# SCB_CLKs.net
KiCad netlist of a schematic drawn in Altium Designer
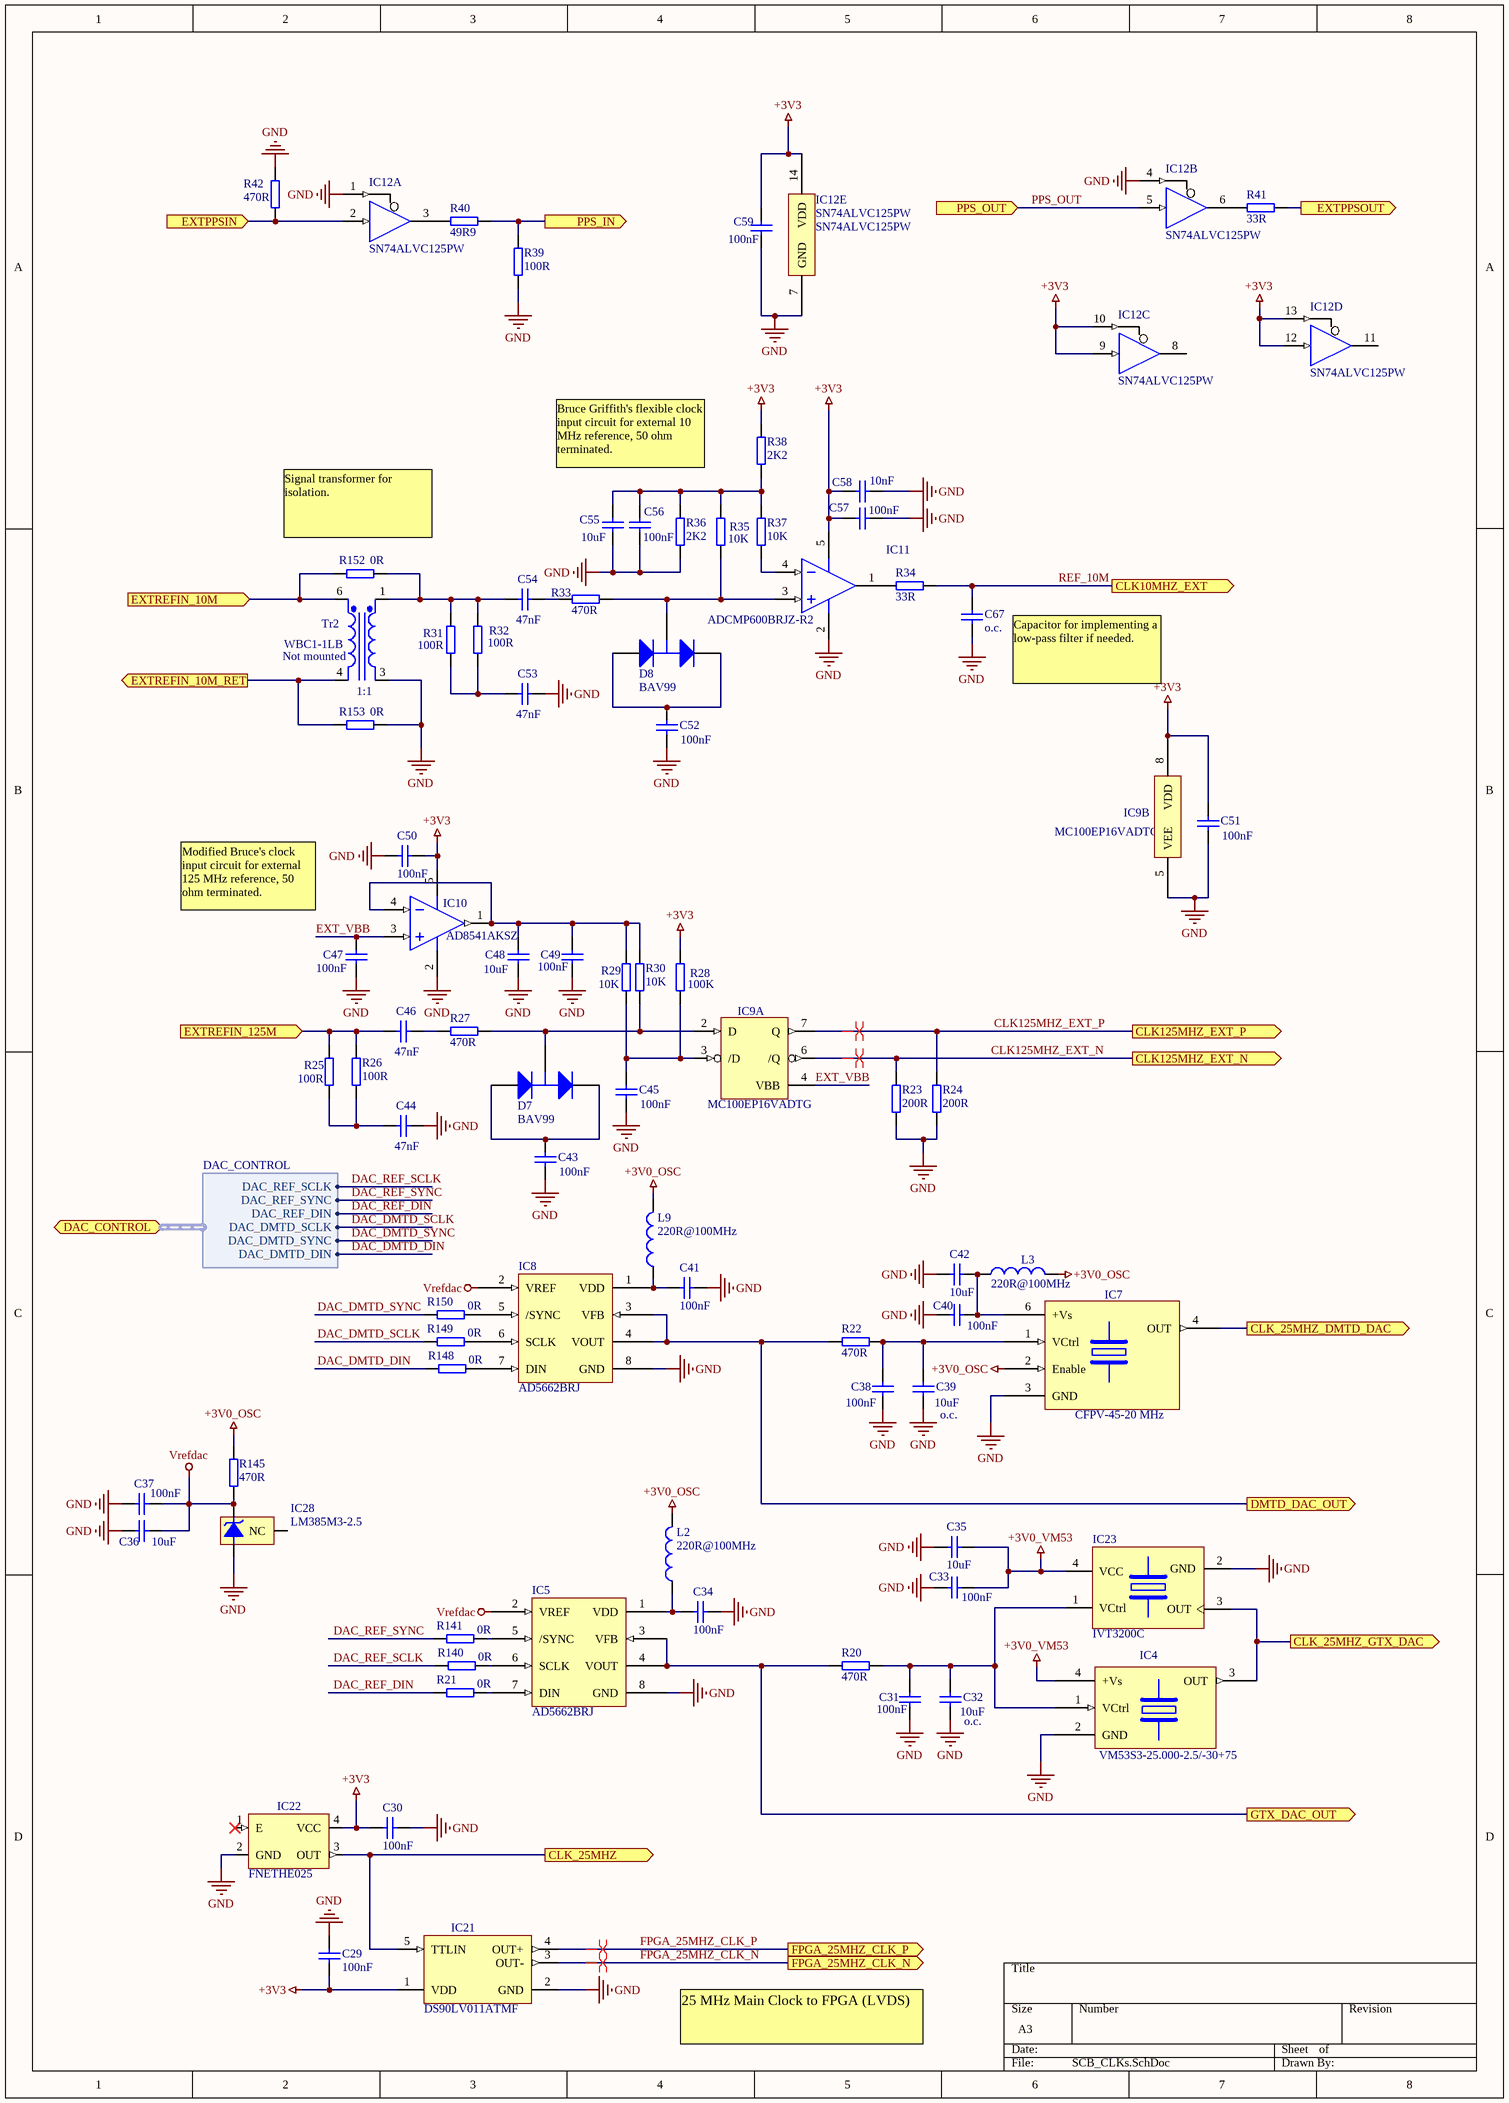
[diagram p0: SCB_CLKs.SchDoc]

(export (version "E")
  (design (tool "Eeschema 10.0.6"))
  (components
    (comp (ref "C29")
      (value "100nF")
      (footprint "CC1005-0402")
      (description "Capacitor")
      (fields
        (field (name "TOLERANCE") "±10%")
        (field (name "VOLTAGE") "16V")
        (field (name "PUBLISHER") "Altium Limited")
      )
      (libsource (lib "wr_switch") (part "Cap"))
    )
    (comp (ref "C30")
      (value "100nF")
      (footprint "CC1005-0402")
      (description "Capacitor")
      (fields
        (field (name "TOLERANCE") "±10%")
        (field (name "VOLTAGE") "16V")
        (field (name "PUBLISHER") "Altium Limited")
      )
      (libsource (lib "wr_switch") (part "Cap"))
    )
    (comp (ref "C31")
      (value "100nF")
      (footprint "CC1005-0402")
      (description "Capacitor")
      (fields
        (field (name "TOLERANCE") "±10%")
        (field (name "VOLTAGE") "16V")
        (field (name "PUBLISHER") "Altium Limited")
      )
      (libsource (lib "wr_switch") (part "Cap"))
    )
    (comp (ref "C32")
      (value "10uF")
      (footprint "CC1608-0603")
      (description "Capacitor")
      (fields
        (field (name "TOLERANCE") "±20%")
        (field (name "VOLTAGE") "6.3V")
        (field (name "ALTIUM_VALUE") "o.c.")
        (field (name "PUBLISHER") "Altium Limited")
      )
      (libsource (lib "wr_switch") (part "Cap"))
    )
    (comp (ref "C33")
      (value "100nF")
      (footprint "CC1005-0402")
      (description "Capacitor")
      (fields
        (field (name "TOLERANCE") "±10%")
        (field (name "VOLTAGE") "16V")
        (field (name "PUBLISHER") "Altium Limited")
      )
      (libsource (lib "wr_switch") (part "Cap"))
    )
    (comp (ref "C34")
      (value "100nF")
      (footprint "CC1005-0402")
      (description "Capacitor")
      (fields
        (field (name "TOLERANCE") "±10%")
        (field (name "VOLTAGE") "16V")
        (field (name "PUBLISHER") "Altium Limited")
      )
      (libsource (lib "wr_switch") (part "Cap"))
    )
    (comp (ref "C35")
      (value "10uF")
      (footprint "CC1608-0603")
      (description "Capacitor")
      (fields
        (field (name "TOLERANCE") "±20%")
        (field (name "VOLTAGE") "6.3V")
        (field (name "PUBLISHER") "Altium Limited")
      )
      (libsource (lib "wr_switch") (part "Cap"))
    )
    (comp (ref "C36")
      (value "10uF")
      (footprint "CC1608-0603")
      (description "Capacitor")
      (fields
        (field (name "TOLERANCE") "±20%")
        (field (name "VOLTAGE") "6.3V")
        (field (name "PUBLISHER") "Altium Limited")
      )
      (libsource (lib "wr_switch") (part "Cap"))
    )
    (comp (ref "C37")
      (value "100nF")
      (footprint "CC1005-0402")
      (description "Capacitor")
      (fields
        (field (name "TOLERANCE") "±10%")
        (field (name "VOLTAGE") "16V")
        (field (name "PUBLISHER") "Altium Limited")
      )
      (libsource (lib "wr_switch") (part "Cap"))
    )
    (comp (ref "C38")
      (value "100nF")
      (footprint "CC1005-0402")
      (description "Capacitor")
      (fields
        (field (name "TOLERANCE") "±10%")
        (field (name "VOLTAGE") "16V")
        (field (name "PUBLISHER") "Altium Limited")
      )
      (libsource (lib "wr_switch") (part "Cap"))
    )
    (comp (ref "C39")
      (value "10uF")
      (footprint "CC1608-0603")
      (description "Capacitor")
      (fields
        (field (name "TOLERANCE") "±20%")
        (field (name "VOLTAGE") "6.3V")
        (field (name "ALTIUM_VALUE") "o.c.")
        (field (name "PUBLISHER") "Altium Limited")
      )
      (libsource (lib "wr_switch") (part "Cap"))
    )
    (comp (ref "C40")
      (value "100nF")
      (footprint "CC1005-0402")
      (description "Capacitor")
      (fields
        (field (name "TOLERANCE") "±10%")
        (field (name "VOLTAGE") "16V")
        (field (name "PUBLISHER") "Altium Limited")
      )
      (libsource (lib "wr_switch") (part "Cap"))
    )
    (comp (ref "C41")
      (value "100nF")
      (footprint "CC1005-0402")
      (description "Capacitor")
      (fields
        (field (name "TOLERANCE") "±10%")
        (field (name "VOLTAGE") "16V")
        (field (name "PUBLISHER") "Altium Limited")
      )
      (libsource (lib "wr_switch") (part "Cap"))
    )
    (comp (ref "C42")
      (value "10uF")
      (footprint "CC1608-0603")
      (description "Capacitor")
      (fields
        (field (name "TOLERANCE") "±20%")
        (field (name "VOLTAGE") "6.3V")
        (field (name "PUBLISHER") "Altium Limited")
      )
      (libsource (lib "wr_switch") (part "Cap"))
    )
    (comp (ref "C43")
      (value "100nF")
      (footprint "CC1005-0402")
      (description "Capacitor")
      (fields
        (field (name "TOLERANCE") "±10%")
        (field (name "VOLTAGE") "16V")
        (field (name "PUBLISHER") "Altium Limited")
      )
      (libsource (lib "wr_switch") (part "Cap"))
    )
    (comp (ref "C44")
      (value "47nF")
      (footprint "CC1005-0402")
      (description "Capacitor")
      (fields
        (field (name "TOLERANCE") "±10%")
        (field (name "VOLTAGE") "25V")
        (field (name "PUBLISHER") "Altium Limited")
      )
      (libsource (lib "wr_switch") (part "Cap"))
    )
    (comp (ref "C45")
      (value "100nF")
      (footprint "CC1005-0402")
      (description "Capacitor")
      (fields
        (field (name "TOLERANCE") "±10%")
        (field (name "VOLTAGE") "16V")
        (field (name "PUBLISHER") "Altium Limited")
      )
      (libsource (lib "wr_switch") (part "Cap"))
    )
    (comp (ref "C46")
      (value "47nF")
      (footprint "CC1005-0402")
      (description "Capacitor")
      (fields
        (field (name "TOLERANCE") "±10%")
        (field (name "VOLTAGE") "25V")
        (field (name "PUBLISHER") "Altium Limited")
      )
      (libsource (lib "wr_switch") (part "Cap"))
    )
    (comp (ref "C47")
      (value "100nF")
      (footprint "CC1005-0402")
      (description "Capacitor")
      (fields
        (field (name "TOLERANCE") "±10%")
        (field (name "VOLTAGE") "16V")
        (field (name "PUBLISHER") "Altium Limited")
      )
      (libsource (lib "wr_switch") (part "Cap"))
    )
    (comp (ref "C48")
      (value "10uF")
      (footprint "CC1608-0603")
      (description "Capacitor")
      (fields
        (field (name "TOLERANCE") "±20%")
        (field (name "VOLTAGE") "6.3V")
        (field (name "PUBLISHER") "Altium Limited")
      )
      (libsource (lib "wr_switch") (part "Cap"))
    )
    (comp (ref "C49")
      (value "100nF")
      (footprint "CC1005-0402")
      (description "Capacitor")
      (fields
        (field (name "TOLERANCE") "±10%")
        (field (name "VOLTAGE") "16V")
        (field (name "PUBLISHER") "Altium Limited")
      )
      (libsource (lib "wr_switch") (part "Cap"))
    )
    (comp (ref "C50")
      (value "100nF")
      (footprint "CC1005-0402")
      (description "Capacitor")
      (fields
        (field (name "TOLERANCE") "±10%")
        (field (name "VOLTAGE") "16V")
        (field (name "PUBLISHER") "Altium Limited")
      )
      (libsource (lib "wr_switch") (part "Cap"))
    )
    (comp (ref "C51")
      (value "100nF")
      (footprint "CC1005-0402")
      (description "Capacitor")
      (fields
        (field (name "TOLERANCE") "±10%")
        (field (name "VOLTAGE") "16V")
        (field (name "PUBLISHER") "Altium Limited")
      )
      (libsource (lib "wr_switch") (part "Cap"))
    )
    (comp (ref "C52")
      (value "100nF")
      (footprint "CC1005-0402")
      (description "Capacitor")
      (fields
        (field (name "TOLERANCE") "±10%")
        (field (name "VOLTAGE") "16V")
        (field (name "PUBLISHER") "Altium Limited")
      )
      (libsource (lib "wr_switch") (part "Cap"))
    )
    (comp (ref "C53")
      (value "47nF")
      (footprint "CC1005-0402")
      (description "Capacitor")
      (fields
        (field (name "TOLERANCE") "±10%")
        (field (name "VOLTAGE") "25V")
        (field (name "PUBLISHER") "Altium Limited")
      )
      (libsource (lib "wr_switch") (part "Cap"))
    )
    (comp (ref "C54")
      (value "47nF")
      (footprint "CC1005-0402")
      (description "Capacitor")
      (fields
        (field (name "TOLERANCE") "±10%")
        (field (name "VOLTAGE") "25V")
        (field (name "PUBLISHER") "Altium Limited")
      )
      (libsource (lib "wr_switch") (part "Cap"))
    )
    (comp (ref "C55")
      (value "10uF")
      (footprint "CC1608-0603")
      (description "Capacitor")
      (fields
        (field (name "TOLERANCE") "±20%")
        (field (name "VOLTAGE") "6.3V")
        (field (name "PUBLISHER") "Altium Limited")
      )
      (libsource (lib "wr_switch") (part "Cap"))
    )
    (comp (ref "C56")
      (value "100nF")
      (footprint "CC1005-0402")
      (description "Capacitor")
      (fields
        (field (name "TOLERANCE") "±10%")
        (field (name "VOLTAGE") "16V")
        (field (name "PUBLISHER") "Altium Limited")
      )
      (libsource (lib "wr_switch") (part "Cap"))
    )
    (comp (ref "C57")
      (value "100nF")
      (footprint "CC1005-0402")
      (description "Capacitor")
      (fields
        (field (name "TOLERANCE") "±10%")
        (field (name "VOLTAGE") "16V")
        (field (name "PUBLISHER") "Altium Limited")
      )
      (libsource (lib "wr_switch") (part "Cap"))
    )
    (comp (ref "C58")
      (value "10nF")
      (footprint "CC1005-0402")
      (description "Capacitor")
      (fields
        (field (name "TOLERANCE") "±10%")
        (field (name "VOLTAGE") "25V")
        (field (name "PUBLISHER") "Altium Limited")
      )
      (libsource (lib "wr_switch") (part "Cap"))
    )
    (comp (ref "C59")
      (value "100nF")
      (footprint "CC1005-0402")
      (description "Capacitor")
      (fields
        (field (name "TOLERANCE") "±10%")
        (field (name "VOLTAGE") "16V")
        (field (name "PUBLISHER") "Altium Limited")
      )
      (libsource (lib "wr_switch") (part "Cap"))
    )
    (comp (ref "C67")
      (value "o.c.")
      (footprint "CC1608-0603")
      (description "Capacitor")
      (fields
        (field (name "TOLERANCE") "±10%")
        (field (name "VOLTAGE") "16V")
        (field (name "PUBLISHER") "Altium Limited")
      )
      (libsource (lib "wr_switch") (part "Cap"))
    )
    (comp (ref "D7")
      (value "BAV99")
      (footprint "SOT-23")
      (description "Silicon Switching Diode Array for High-Speed Switching")
      (fields (field (name "PUBLISHER") "Altium Limited"))
      (libsource (lib "Infineon Discrete Diode") (part "BAV99"))
    )
    (comp (ref "D8")
      (value "BAV99")
      (footprint "SOT-23")
      (description "Silicon Switching Diode Array for High-Speed Switching")
      (fields (field (name "PUBLISHER") "Altium Limited"))
      (libsource (lib "Infineon Discrete Diode") (part "BAV99"))
    )
    (comp (ref "IC4")
      (value "VM53S3-25.000-2.5/-30+75")
      (footprint "VCTCXO_VM53S")
      (description "VCTCXO oscillator")
      (libsource (lib "wr_switch") (part "VCTCXO_VM53S"))
    )
    (comp (ref "IC5")
      (value "AD5662BRJ")
      (footprint "SOT23-8")
      (description "Analog Devices 16-bit DAC w/SPI interface, ext ref")
      (fields (field (name "Comment") "AD5662B"))
      (libsource (lib "wr_switch") (part "AD5662"))
    )
    (comp (ref "IC7")
      (value "CFPV-45-20 MHz")
      (footprint "vs-705")
      (description "VCXO oscillator")
      (fields (field (name "MANUFACTURER") "IQD Frequency"))
      (libsource (lib "wr_switch") (part "VCXO_CFPV_45"))
    )
    (comp (ref "IC8")
      (value "AD5662BRJ")
      (footprint "SOT23-8")
      (description "Analog Devices 16-bit DAC w/SPI interface, ext ref")
      (fields (field (name "Comment") "AD5662B"))
      (libsource (lib "wr_switch") (part "AD5662"))
    )
    (comp (ref "IC9")
      (value "MC100EP16VADTG")
      (footprint "TSOP65P490-8AN")
      (description "ONSemi differental receiver w/ECL output")
      (fields (field (name "Comment") "MC100EP16"))
      (libsource (lib "wr_switch") (part "MC100EP16"))
    )
    (comp (ref "IC10")
      (value "AD8541AKSZ")
      (footprint "SOT65P210X110-5N")
      (description "Analog Devices general purpose low-voltage R2R CMOS opamp")
      (libsource (lib "wr_switch") (part "AD8541"))
    )
    (comp (ref "IC11")
      (value "ADCMP600BRJZ-R2")
      (footprint "SOT23-5AL")
      (description "Analog Devices fast comparator")
      (libsource (lib "wr_switch") (part "ADCMP600"))
    )
    (comp (ref "IC12")
      (value "SN74ALVC125PW")
      (footprint "PW014")
      (description "Quad Buffer with 3-State Outputs with TTL Compatible Inputs")
      (fields (field (name "ALTIUM_VALUE") "SN74ALVC125PW") (field (name "Comment") "SN74ALVC125"))
      (libsource (lib "wr_switch") (part "SN74ALVC125"))
    )
    (comp (ref "IC21")
      (value "DS90LV011ATMF")
      (footprint "MF05A_N")
      (description "Single High Speed Differential Driver")
      (fields
        (field (name "MANUFACTURER") "National Semiconductor")
        (field (name "DIGIKEYPARTNUMBER") "DS90LV011ATMFTR-ND")
        (field (name "PUBLISHER") "Altium Limited")
      )
      (libsource (lib "NSC Interface") (part "DS90LV011ATMF"))
    )
    (comp (ref "IC22")
      (value "FNETHE025")
      (footprint "SPXO")
      (description "SMD oscillator 3.3V (Elfa)")
      (libsource (lib "wr_switch") (part "OSC_CFPS-73"))
    )
    (comp (ref "IC23")
      (value "IVT3200C")
      (footprint "OSC_RAKON_IVT3200C")
      (libsource (lib "wr_switch") (part "IVT32000C"))
    )
    (comp (ref "IC28")
      (value "LM385M3-2.5")
      (footprint "MF03A_N")
      (description "Micropower Voltage Reference Diode")
      (fields
        (field (name "MANUFACTURER") "National Semiconductor")
        (field (name "DIGIKEYPARTNUMBER") "LM385M3-2.5CT-ND")
        (field (name "PUBLISHER") "Altium Limited")
      )
      (libsource (lib "NSC Voltage Reference") (part "LM385M3-2.5"))
    )
    (comp (ref "L2")
      (value "220R@100MHz Ferrite Bead")
      (footprint "0603")
      (description "ferrite bead")
      (fields (field (name "IMPEDANCE") "220R@100MHz"))
      (libsource (lib "wr_switch") (part "L_FERRITE_BEAD"))
    )
    (comp (ref "L3")
      (value "220R@100MHz Ferrite Bead")
      (footprint "0603")
      (description "ferrite bead")
      (fields (field (name "IMPEDANCE") "220R@100MHz"))
      (libsource (lib "wr_switch") (part "L_FERRITE_BEAD"))
    )
    (comp (ref "L9")
      (value "220R@100MHz Ferrite Bead")
      (footprint "0603")
      (description "ferrite bead")
      (fields (field (name "IMPEDANCE") "220R@100MHz"))
      (libsource (lib "wr_switch") (part "L_FERRITE_BEAD"))
    )
    (comp (ref "R20")
      (value "470R")
      (footprint "0402")
      (description "SMD Resistor")
      (fields (field (name "TOLERANCE") "±1%"))
      (libsource (lib "wr_switch") (part "RES_SMD"))
    )
    (comp (ref "R21")
      (value "0R")
      (footprint "0603")
      (description "SMD Resistor")
      (libsource (lib "wr_switch") (part "RES_SMD"))
    )
    (comp (ref "R22")
      (value "470R")
      (footprint "0402")
      (description "SMD Resistor")
      (fields (field (name "TOLERANCE") "±1%"))
      (libsource (lib "wr_switch") (part "RES_SMD"))
    )
    (comp (ref "R23")
      (value "200R")
      (footprint "0402")
      (description "SMD Resistor")
      (fields (field (name "TOLERANCE") "±1%"))
      (libsource (lib "wr_switch") (part "RES_SMD"))
    )
    (comp (ref "R24")
      (value "200R")
      (footprint "0402")
      (description "SMD Resistor")
      (fields (field (name "TOLERANCE") "±1%"))
      (libsource (lib "wr_switch") (part "RES_SMD"))
    )
    (comp (ref "R25")
      (value "100R")
      (footprint "0402")
      (description "SMD Resistor")
      (fields (field (name "TOLERANCE") "±1%"))
      (libsource (lib "wr_switch") (part "RES_SMD"))
    )
    (comp (ref "R26")
      (value "100R")
      (footprint "0402")
      (description "SMD Resistor")
      (fields (field (name "TOLERANCE") "±1%"))
      (libsource (lib "wr_switch") (part "RES_SMD"))
    )
    (comp (ref "R27")
      (value "470R")
      (footprint "0402")
      (description "SMD Resistor")
      (fields (field (name "TOLERANCE") "±1%"))
      (libsource (lib "wr_switch") (part "RES_SMD"))
    )
    (comp (ref "R28")
      (value "100K")
      (footprint "0402")
      (description "SMD Resistor")
      (fields (field (name "TOLERANCE") "±1%"))
      (libsource (lib "wr_switch") (part "RES_SMD"))
    )
    (comp (ref "R29")
      (value "10K")
      (footprint "0402")
      (description "SMD Resistor")
      (fields (field (name "TOLERANCE") "±1%") (field (name "Comment") "10k"))
      (libsource (lib "wr_switch") (part "RES_SMD"))
    )
    (comp (ref "R30")
      (value "10K")
      (footprint "0402")
      (description "SMD Resistor")
      (fields (field (name "TOLERANCE") "±1%") (field (name "Comment") "10k"))
      (libsource (lib "wr_switch") (part "RES_SMD"))
    )
    (comp (ref "R31")
      (value "100R")
      (footprint "0402")
      (description "SMD Resistor")
      (fields (field (name "TOLERANCE") "±1%"))
      (libsource (lib "wr_switch") (part "RES_SMD"))
    )
    (comp (ref "R32")
      (value "100R")
      (footprint "0402")
      (description "SMD Resistor")
      (fields (field (name "TOLERANCE") "±1%"))
      (libsource (lib "wr_switch") (part "RES_SMD"))
    )
    (comp (ref "R33")
      (value "470R")
      (footprint "0402")
      (description "SMD Resistor")
      (fields (field (name "TOLERANCE") "±1%"))
      (libsource (lib "wr_switch") (part "RES_SMD"))
    )
    (comp (ref "R34")
      (value "33R")
      (footprint "0603")
      (description "SMD Resistor")
      (fields (field (name "TOLERANCE") "±1%"))
      (libsource (lib "wr_switch") (part "RES_SMD"))
    )
    (comp (ref "R35")
      (value "10K")
      (footprint "0402")
      (description "SMD Resistor")
      (fields (field (name "TOLERANCE") "±1%") (field (name "Comment") "10k"))
      (libsource (lib "wr_switch") (part "RES_SMD"))
    )
    (comp (ref "R36")
      (value "2K2")
      (footprint "0402")
      (description "SMD Resistor")
      (fields (field (name "TOLERANCE") "±1%"))
      (libsource (lib "wr_switch") (part "RES_SMD"))
    )
    (comp (ref "R37")
      (value "10K")
      (footprint "0402")
      (description "SMD Resistor")
      (fields (field (name "TOLERANCE") "±1%") (field (name "Comment") "10k"))
      (libsource (lib "wr_switch") (part "RES_SMD"))
    )
    (comp (ref "R38")
      (value "2K2")
      (footprint "0402")
      (description "SMD Resistor")
      (fields (field (name "TOLERANCE") "±1%"))
      (libsource (lib "wr_switch") (part "RES_SMD"))
    )
    (comp (ref "R39")
      (value "100R")
      (footprint "0402")
      (description "SMD Resistor")
      (fields (field (name "TOLERANCE") "±1%"))
      (libsource (lib "wr_switch") (part "RES_SMD"))
    )
    (comp (ref "R40")
      (value "49R9")
      (footprint "0603")
      (description "SMD Resistor")
      (fields (field (name "TOLERANCE") "±1%"))
      (libsource (lib "wr_switch") (part "RES_SMD"))
    )
    (comp (ref "R41")
      (value "33R")
      (footprint "0603")
      (description "SMD Resistor")
      (fields (field (name "TOLERANCE") "±1%"))
      (libsource (lib "wr_switch") (part "RES_SMD"))
    )
    (comp (ref "R42")
      (value "470R")
      (footprint "0402")
      (description "SMD Resistor")
      (fields (field (name "TOLERANCE") "±1%"))
      (libsource (lib "wr_switch") (part "RES_SMD"))
    )
    (comp (ref "R140")
      (value "0R")
      (footprint "0603")
      (description "SMD Resistor")
      (libsource (lib "wr_switch") (part "RES_SMD"))
    )
    (comp (ref "R141")
      (value "0R")
      (footprint "0603")
      (description "SMD Resistor")
      (libsource (lib "wr_switch") (part "RES_SMD"))
    )
    (comp (ref "R145")
      (value "470R")
      (footprint "0402")
      (description "SMD Resistor")
      (fields (field (name "TOLERANCE") "±1%"))
      (libsource (lib "wr_switch") (part "RES_SMD"))
    )
    (comp (ref "R148")
      (value "0R")
      (footprint "0603")
      (description "SMD Resistor")
      (libsource (lib "wr_switch") (part "RES_SMD"))
    )
    (comp (ref "R149")
      (value "0R")
      (footprint "0603")
      (description "SMD Resistor")
      (libsource (lib "wr_switch") (part "RES_SMD"))
    )
    (comp (ref "R150")
      (value "0R")
      (footprint "0603")
      (description "SMD Resistor")
      (libsource (lib "wr_switch") (part "RES_SMD"))
    )
    (comp (ref "R152")
      (value "0R")
      (footprint "0402")
      (description "SMD Resistor")
      (fields (field (name "TOLERANCE") "Jumper"))
      (libsource (lib "wr_switch") (part "RES_SMD"))
    )
    (comp (ref "R153")
      (value "0R")
      (footprint "0402")
      (description "SMD Resistor")
      (fields (field (name "TOLERANCE") "Jumper"))
      (libsource (lib "wr_switch") (part "RES_SMD"))
    )
    (comp (ref "Tr2")
      (value "WBC1-1LB")
      (footprint "SMT6P150P")
      (description "SMT Mini WideBand Transformer 1:1, 10uH,")
      (fields
        (field (name "MANUFACTURER") "Coilcraft")
        (field (name "ALTIUM_VALUE") "1:1")
        (field (name "MOUNTED") "Not mounted")
        (field (name "PUBLISHER") "Altium Limited")
      )
      (libsource (lib "wr_switch") (part "WBC1-1LB"))
    )
  )
  (nets
    (net (code "2") (name "+3V0_OSC") (class "Default")
      (node (ref "IC7") (pin "2") (pinfunction "Enable_2") (pintype "input"))
      (node (ref "L2") (pin "2") (pinfunction "2_2") (pintype "passive"))
      (node (ref "L3") (pin "2") (pinfunction "2_2") (pintype "passive"))
      (node (ref "L9") (pin "2") (pinfunction "2_2") (pintype "passive"))
      (node (ref "R145") (pin "2") (pinfunction "2_2") (pintype "passive"))
    )
    (net (code "3") (name "+3V0_VM53") (class "Default")
      (node (ref "C33") (pin "1") (pinfunction "1_1") (pintype "passive"))
      (node (ref "C35") (pin "1") (pinfunction "1_1") (pintype "passive"))
      (node (ref "IC23") (pin "4") (pinfunction "VCC_4") (pintype "power_in"))
      (node (ref "IC4") (pin "4") (pinfunction "+Vs_4") (pintype "power_in"))
    )
    (net (code "4") (name "+3V3") (class "Default")
      (node (ref "C29") (pin "2") (pinfunction "2_2") (pintype "passive"))
      (node (ref "C30") (pin "2") (pinfunction "2_2") (pintype "passive"))
      (node (ref "C50") (pin "1") (pinfunction "1_1") (pintype "passive"))
      (node (ref "C51") (pin "2") (pinfunction "2_2") (pintype "passive"))
      (node (ref "C57") (pin "2") (pinfunction "2_2") (pintype "passive"))
      (node (ref "C58") (pin "2") (pinfunction "2_2") (pintype "passive"))
      (node (ref "C59") (pin "2") (pinfunction "2_2") (pintype "passive"))
      (node (ref "IC10") (pin "5") (pinfunction "V+_5") (pintype "power_in"))
      (node (ref "IC11") (pin "5") (pinfunction "VCC/VCCO_5") (pintype "power_in"))
      (node (ref "IC12") (pin "10") (pinfunction "~{A}_10") (pintype "input"))
      (node (ref "IC12") (pin "12") (pinfunction "B_12") (pintype "input"))
      (node (ref "IC12") (pin "13") (pinfunction "~{A}_13") (pintype "input"))
      (node (ref "IC12") (pin "14") (pinfunction "VDD_14") (pintype "passive"))
      (node (ref "IC12") (pin "9") (pinfunction "B_9") (pintype "input"))
      (node (ref "IC21") (pin "1") (pinfunction "VDD_1") (pintype "power_in"))
      (node (ref "IC22") (pin "4") (pinfunction "VCC_4") (pintype "power_in"))
      (node (ref "IC9") (pin "8") (pinfunction "VDD_8") (pintype "passive"))
      (node (ref "R28") (pin "2") (pinfunction "2_2") (pintype "passive"))
      (node (ref "R38") (pin "2") (pinfunction "2_2") (pintype "passive"))
    )
    (net (code "5") (name "/CLK125MHZ_EXT_N") (class "Default")
      (node (ref "IC9") (pin "6") (pinfunction "/Q_6") (pintype "output"))
      (node (ref "R23") (pin "2") (pinfunction "2_2") (pintype "passive"))
    )
    (net (code "6") (name "/CLK125MHZ_EXT_P") (class "Default")
      (node (ref "IC9") (pin "7") (pinfunction "Q_7") (pintype "output"))
      (node (ref "R24") (pin "2") (pinfunction "2_2") (pintype "passive"))
    )
    (net (code "7") (name "/CLK_25MHZ") (class "Default")
      (node (ref "IC21") (pin "5") (pinfunction "TTLIN_5") (pintype "input"))
      (node (ref "IC22") (pin "3") (pinfunction "OUT_3") (pintype "output"))
    )
    (net (code "8") (name "/CLK_25MHZ_DMTD_DAC") (class "Default")
      (node (ref "IC7") (pin "4") (pinfunction "OUT_4") (pintype "output"))
    )
    (net (code "9") (name "/CLK_25MHZ_GTX_DAC") (class "Default")
      (node (ref "IC23") (pin "3") (pinfunction "OUT_3") (pintype "passive"))
      (node (ref "IC4") (pin "3") (pinfunction "OUT_3") (pintype "output"))
    )
    (net (code "10") (name "/DAC_DMTD_DIN") (class "Default")
      (node (ref "R148") (pin "2") (pinfunction "2_2") (pintype "passive"))
    )
    (net (code "11") (name "/DAC_DMTD_SCLK") (class "Default")
      (node (ref "R149") (pin "2") (pinfunction "2_2") (pintype "passive"))
    )
    (net (code "12") (name "/DAC_DMTD_SYNC") (class "Default")
      (node (ref "R150") (pin "2") (pinfunction "2_2") (pintype "passive"))
    )
    (net (code "13") (name "/DAC_REF_DIN") (class "Default")
      (node (ref "R21") (pin "2") (pinfunction "2_2") (pintype "passive"))
    )
    (net (code "14") (name "/DAC_REF_SCLK") (class "Default")
      (node (ref "R140") (pin "2") (pinfunction "2_2") (pintype "passive"))
    )
    (net (code "15") (name "/DAC_REF_SYNC") (class "Default")
      (node (ref "R141") (pin "2") (pinfunction "2_2") (pintype "passive"))
    )
    (net (code "16") (name "/DMTD_DAC_OUT") (class "Default")
      (node (ref "IC8") (pin "3") (pinfunction "VFB_3") (pintype "input"))
      (node (ref "IC8") (pin "4") (pinfunction "VOUT_4") (pintype "power_in"))
      (node (ref "R22") (pin "1") (pinfunction "1_1") (pintype "passive"))
    )
    (net (code "17") (name "/EXTPPSIN") (class "Default")
      (node (ref "IC12") (pin "2") (pinfunction "B_2") (pintype "input"))
      (node (ref "R42") (pin "1") (pinfunction "1_1") (pintype "passive"))
    )
    (net (code "18") (name "/EXTPPSOUT") (class "Default")
      (node (ref "R41") (pin "2") (pinfunction "2_2") (pintype "passive"))
    )
    (net (code "19") (name "/EXTREFIN_10M") (class "Default")
      (node (ref "R152") (pin "2") (pinfunction "2_2") (pintype "passive"))
      (node (ref "Tr2") (pin "6") (pinfunction "Pri+_6") (pintype "passive"))
    )
    (net (code "20") (name "/EXTREFIN_10M_RET") (class "Default")
      (node (ref "R153") (pin "2") (pinfunction "2_2") (pintype "passive"))
      (node (ref "Tr2") (pin "4") (pinfunction "Pri-_4") (pintype "passive"))
    )
    (net (code "21") (name "/EXTREFIN_125M") (class "Default")
      (node (ref "C46") (pin "1") (pinfunction "1_1") (pintype "passive"))
      (node (ref "R25") (pin "2") (pinfunction "2_2") (pintype "passive"))
      (node (ref "R26") (pin "2") (pinfunction "2_2") (pintype "passive"))
    )
    (net (code "22") (name "/EXT_VBB") (class "Default")
      (node (ref "C47") (pin "2") (pinfunction "2_2") (pintype "passive"))
      (node (ref "IC10") (pin "3") (pinfunction "IN+_3") (pintype "input"))
      (node (ref "IC9") (pin "4") (pinfunction "VBB_4") (pintype "passive"))
    )
    (net (code "23") (name "/FPGA_25MHZ_CLK_N") (class "Default")
      (node (ref "IC21") (pin "3") (pinfunction "OUT-_3") (pintype "output"))
    )
    (net (code "24") (name "/FPGA_25MHZ_CLK_P") (class "Default")
      (node (ref "IC21") (pin "4") (pinfunction "OUT+_4") (pintype "output"))
    )
    (net (code "25") (name "/GTX_DAC_OUT") (class "Default")
      (node (ref "IC5") (pin "3") (pinfunction "VFB_3") (pintype "input"))
      (node (ref "IC5") (pin "4") (pinfunction "VOUT_4") (pintype "power_in"))
      (node (ref "R20") (pin "1") (pinfunction "1_1") (pintype "passive"))
    )
    (net (code "26") (name "/PPS_IN") (class "Default")
      (node (ref "R39") (pin "2") (pinfunction "2_2") (pintype "passive"))
      (node (ref "R40") (pin "2") (pinfunction "2_2") (pintype "passive"))
    )
    (net (code "27") (name "/PPS_OUT") (class "Default")
      (node (ref "IC12") (pin "5") (pinfunction "B_5") (pintype "input"))
    )
    (net (code "28") (name "/REF_10M") (class "Default")
      (node (ref "C67") (pin "2") (pinfunction "2_2") (pintype "passive"))
      (node (ref "R34") (pin "2") (pinfunction "2_2") (pintype "passive"))
    )
    (net (code "30") (name "GND") (class "Default")
      (node (ref "C29") (pin "1") (pinfunction "1_1") (pintype "passive"))
      (node (ref "C30") (pin "1") (pinfunction "1_1") (pintype "passive"))
      (node (ref "C31") (pin "1") (pinfunction "1_1") (pintype "passive"))
      (node (ref "C32") (pin "1") (pinfunction "1_1") (pintype "passive"))
      (node (ref "C33") (pin "2") (pinfunction "2_2") (pintype "passive"))
      (node (ref "C34") (pin "1") (pinfunction "1_1") (pintype "passive"))
      (node (ref "C35") (pin "2") (pinfunction "2_2") (pintype "passive"))
      (node (ref "C36") (pin "1") (pinfunction "1_1") (pintype "passive"))
      (node (ref "C37") (pin "2") (pinfunction "2_2") (pintype "passive"))
      (node (ref "C38") (pin "1") (pinfunction "1_1") (pintype "passive"))
      (node (ref "C39") (pin "1") (pinfunction "1_1") (pintype "passive"))
      (node (ref "C40") (pin "2") (pinfunction "2_2") (pintype "passive"))
      (node (ref "C41") (pin "1") (pinfunction "1_1") (pintype "passive"))
      (node (ref "C42") (pin "2") (pinfunction "2_2") (pintype "passive"))
      (node (ref "C43") (pin "1") (pinfunction "1_1") (pintype "passive"))
      (node (ref "C44") (pin "2") (pinfunction "2_2") (pintype "passive"))
      (node (ref "C45") (pin "1") (pinfunction "1_1") (pintype "passive"))
      (node (ref "C47") (pin "1") (pinfunction "1_1") (pintype "passive"))
      (node (ref "C48") (pin "1") (pinfunction "1_1") (pintype "passive"))
      (node (ref "C49") (pin "1") (pinfunction "1_1") (pintype "passive"))
      (node (ref "C50") (pin "2") (pinfunction "2_2") (pintype "passive"))
      (node (ref "C51") (pin "1") (pinfunction "1_1") (pintype "passive"))
      (node (ref "C52") (pin "1") (pinfunction "1_1") (pintype "passive"))
      (node (ref "C53") (pin "2") (pinfunction "2_2") (pintype "passive"))
      (node (ref "C55") (pin "1") (pinfunction "1_1") (pintype "passive"))
      (node (ref "C56") (pin "1") (pinfunction "1_1") (pintype "passive"))
      (node (ref "C57") (pin "1") (pinfunction "1_1") (pintype "passive"))
      (node (ref "C58") (pin "1") (pinfunction "1_1") (pintype "passive"))
      (node (ref "C59") (pin "1") (pinfunction "1_1") (pintype "passive"))
      (node (ref "C67") (pin "1") (pinfunction "1_1") (pintype "passive"))
      (node (ref "IC10") (pin "2") (pinfunction "V-_2") (pintype "power_in"))
      (node (ref "IC11") (pin "2") (pinfunction "VEE_2") (pintype "power_in"))
      (node (ref "IC12") (pin "1") (pinfunction "~{A}_1") (pintype "input"))
      (node (ref "IC12") (pin "4") (pinfunction "~{A}_4") (pintype "input"))
      (node (ref "IC12") (pin "7") (pinfunction "GND_7") (pintype "passive"))
      (node (ref "IC21") (pin "2") (pinfunction "GND_2") (pintype "power_in"))
      (node (ref "IC22") (pin "2") (pinfunction "GND_2") (pintype "power_in"))
      (node (ref "IC23") (pin "2") (pinfunction "GND_2") (pintype "power_in"))
      (node (ref "IC28") (pin "2") (pinfunction "-V_2") (pintype "passive"))
      (node (ref "IC4") (pin "2") (pinfunction "GND_2") (pintype "power_in"))
      (node (ref "IC5") (pin "8") (pinfunction "GND_8") (pintype "power_in"))
      (node (ref "IC7") (pin "3") (pinfunction "GND_3") (pintype "power_in"))
      (node (ref "IC8") (pin "8") (pinfunction "GND_8") (pintype "power_in"))
      (node (ref "IC9") (pin "5") (pinfunction "VEE_5") (pintype "passive"))
      (node (ref "R153") (pin "1") (pinfunction "1_1") (pintype "passive"))
      (node (ref "R23") (pin "1") (pinfunction "1_1") (pintype "passive"))
      (node (ref "R24") (pin "1") (pinfunction "1_1") (pintype "passive"))
      (node (ref "R36") (pin "1") (pinfunction "1_1") (pintype "passive"))
      (node (ref "R39") (pin "1") (pinfunction "1_1") (pintype "passive"))
      (node (ref "R42") (pin "2") (pinfunction "2_2") (pintype "passive"))
      (node (ref "Tr2") (pin "3") (pinfunction "Sec-_3") (pintype "passive"))
    )
    (net (code "31") (name "Net-(C44-Pad1)") (class "Default")
      (node (ref "C44") (pin "1") (pinfunction "1_1") (pintype "passive"))
      (node (ref "R25") (pin "1") (pinfunction "1_1") (pintype "passive"))
      (node (ref "R26") (pin "1") (pinfunction "1_1") (pintype "passive"))
    )
    (net (code "32") (name "Net-(C46-Pad2)") (class "Default")
      (node (ref "C46") (pin "2") (pinfunction "2_2") (pintype "passive"))
      (node (ref "R27") (pin "1") (pinfunction "1_1") (pintype "passive"))
    )
    (net (code "33") (name "Net-(C53-Pad1)") (class "Default")
      (node (ref "C53") (pin "1") (pinfunction "1_1") (pintype "passive"))
      (node (ref "R31") (pin "1") (pinfunction "1_1") (pintype "passive"))
      (node (ref "R32") (pin "1") (pinfunction "1_1") (pintype "passive"))
    )
    (net (code "34") (name "Net-(C54-Pad2)") (class "Default")
      (node (ref "C54") (pin "2") (pinfunction "2_2") (pintype "passive"))
      (node (ref "R33") (pin "1") (pinfunction "1_1") (pintype "passive"))
    )
    (net (code "35") (name "Net-(C55-Pad2)") (class "Default")
      (node (ref "C55") (pin "2") (pinfunction "2_2") (pintype "passive"))
      (node (ref "C56") (pin "2") (pinfunction "2_2") (pintype "passive"))
      (node (ref "R35") (pin "2") (pinfunction "2_2") (pintype "passive"))
      (node (ref "R36") (pin "2") (pinfunction "2_2") (pintype "passive"))
      (node (ref "R37") (pin "2") (pinfunction "2_2") (pintype "passive"))
      (node (ref "R38") (pin "1") (pinfunction "1_1") (pintype "passive"))
    )
    (net (code "36") (name "Net-(D7-A)") (class "Default")
      (node (ref "C43") (pin "2") (pinfunction "2_2") (pintype "passive"))
      (node (ref "D7") (pin "1") (pinfunction "A_1") (pintype "passive"))
      (node (ref "D7") (pin "2") (pinfunction "K_2") (pintype "passive"))
    )
    (net (code "37") (name "Net-(D7-C)") (class "Default")
      (node (ref "D7") (pin "3") (pinfunction "C_3") (pintype "passive"))
      (node (ref "IC9") (pin "2") (pinfunction "D_2") (pintype "input"))
      (node (ref "R27") (pin "2") (pinfunction "2_2") (pintype "passive"))
      (node (ref "R30") (pin "1") (pinfunction "1_1") (pintype "passive"))
    )
    (net (code "38") (name "Net-(D8-A)") (class "Default")
      (node (ref "C52") (pin "2") (pinfunction "2_2") (pintype "passive"))
      (node (ref "D8") (pin "1") (pinfunction "A_1") (pintype "passive"))
      (node (ref "D8") (pin "2") (pinfunction "K_2") (pintype "passive"))
    )
    (net (code "39") (name "Net-(D8-C)") (class "Default")
      (node (ref "D8") (pin "3") (pinfunction "C_3") (pintype "passive"))
      (node (ref "IC11") (pin "3") (pinfunction "VP_3") (pintype "input"))
      (node (ref "R33") (pin "2") (pinfunction "2_2") (pintype "passive"))
      (node (ref "R35") (pin "1") (pinfunction "1_1") (pintype "passive"))
    )
    (net (code "40") (name "Net-(IC5-DIN)") (class "Default")
      (node (ref "IC5") (pin "7") (pinfunction "DIN_7") (pintype "input"))
      (node (ref "R21") (pin "1") (pinfunction "1_1") (pintype "passive"))
    )
    (net (code "41") (name "Net-(IC5-SCLK)") (class "Default")
      (node (ref "IC5") (pin "6") (pinfunction "SCLK_6") (pintype "input"))
      (node (ref "R140") (pin "1") (pinfunction "1_1") (pintype "passive"))
    )
    (net (code "42") (name "Net-(IC5-VDD)") (class "Default")
      (node (ref "C34") (pin "2") (pinfunction "2_2") (pintype "passive"))
      (node (ref "IC5") (pin "1") (pinfunction "VDD_1") (pintype "power_in"))
      (node (ref "L2") (pin "1") (pinfunction "1_1") (pintype "passive"))
    )
    (net (code "43") (name "Net-(IC5-{slash}SYNC)") (class "Default")
      (node (ref "IC5") (pin "5") (pinfunction "/SYNC_5") (pintype "input"))
      (node (ref "R141") (pin "1") (pinfunction "1_1") (pintype "passive"))
    )
    (net (code "44") (name "Net-(IC7-+Vs)") (class "Default")
      (node (ref "C40") (pin "1") (pinfunction "1_1") (pintype "passive"))
      (node (ref "C42") (pin "1") (pinfunction "1_1") (pintype "passive"))
      (node (ref "IC7") (pin "6") (pinfunction "+Vs_6") (pintype "power_in"))
      (node (ref "L3") (pin "1") (pinfunction "1_1") (pintype "passive"))
    )
    (net (code "45") (name "Net-(IC7-VCtrl)") (class "Default")
      (node (ref "C38") (pin "2") (pinfunction "2_2") (pintype "passive"))
      (node (ref "C39") (pin "2") (pinfunction "2_2") (pintype "passive"))
      (node (ref "IC7") (pin "1") (pinfunction "VCtrl_1") (pintype "input"))
      (node (ref "R22") (pin "2") (pinfunction "2_2") (pintype "passive"))
    )
    (net (code "46") (name "Net-(IC8-DIN)") (class "Default")
      (node (ref "IC8") (pin "7") (pinfunction "DIN_7") (pintype "input"))
      (node (ref "R148") (pin "1") (pinfunction "1_1") (pintype "passive"))
    )
    (net (code "47") (name "Net-(IC8-SCLK)") (class "Default")
      (node (ref "IC8") (pin "6") (pinfunction "SCLK_6") (pintype "input"))
      (node (ref "R149") (pin "1") (pinfunction "1_1") (pintype "passive"))
    )
    (net (code "48") (name "Net-(IC8-VDD)") (class "Default")
      (node (ref "C41") (pin "2") (pinfunction "2_2") (pintype "passive"))
      (node (ref "IC8") (pin "1") (pinfunction "VDD_1") (pintype "power_in"))
      (node (ref "L9") (pin "1") (pinfunction "1_1") (pintype "passive"))
    )
    (net (code "49") (name "Net-(IC8-{slash}SYNC)") (class "Default")
      (node (ref "IC8") (pin "5") (pinfunction "/SYNC_5") (pintype "input"))
      (node (ref "R150") (pin "1") (pinfunction "1_1") (pintype "passive"))
    )
    (net (code "50") (name "Net-(IC9A-{slash}D)") (class "Default")
      (node (ref "C45") (pin "2") (pinfunction "2_2") (pintype "passive"))
      (node (ref "IC9") (pin "3") (pinfunction "/D_3") (pintype "input"))
      (node (ref "R28") (pin "1") (pinfunction "1_1") (pintype "passive"))
      (node (ref "R29") (pin "1") (pinfunction "1_1") (pintype "passive"))
    )
    (net (code "51") (name "Net-(IC10-IN-)") (class "Default")
      (node (ref "C48") (pin "2") (pinfunction "2_2") (pintype "passive"))
      (node (ref "C49") (pin "2") (pinfunction "2_2") (pintype "passive"))
      (node (ref "IC10") (pin "1") (pinfunction "OUT_1") (pintype "output"))
      (node (ref "IC10") (pin "4") (pinfunction "IN-_4") (pintype "input"))
      (node (ref "R29") (pin "2") (pinfunction "2_2") (pintype "passive"))
      (node (ref "R30") (pin "2") (pinfunction "2_2") (pintype "passive"))
    )
    (net (code "52") (name "Net-(IC11-Q)") (class "Default")
      (node (ref "IC11") (pin "1") (pinfunction "Q_1") (pintype "open_collector"))
      (node (ref "R34") (pin "1") (pinfunction "1_1") (pintype "passive"))
    )
    (net (code "53") (name "Net-(IC11-VN)") (class "Default")
      (node (ref "IC11") (pin "4") (pinfunction "VN_4") (pintype "input"))
      (node (ref "R37") (pin "1") (pinfunction "1_1") (pintype "passive"))
    )
    (net (code "54") (name "Net-(IC12A-Y)") (class "Default")
      (node (ref "IC12") (pin "3") (pinfunction "Y_3") (pintype "tri_state"))
      (node (ref "R40") (pin "1") (pinfunction "1_1") (pintype "passive"))
    )
    (net (code "55") (name "Net-(IC12B-Y)") (class "Default")
      (node (ref "IC12") (pin "6") (pinfunction "Y_6") (pintype "tri_state"))
      (node (ref "R41") (pin "1") (pinfunction "1_1") (pintype "passive"))
    )
    (net (code "56") (name "Net-(IC23-VCtrl)") (class "Default")
      (node (ref "C31") (pin "2") (pinfunction "2_2") (pintype "passive"))
      (node (ref "C32") (pin "2") (pinfunction "2_2") (pintype "passive"))
      (node (ref "IC23") (pin "1") (pinfunction "VCtrl_1") (pintype "passive"))
      (node (ref "IC4") (pin "1") (pinfunction "VCtrl_1") (pintype "input"))
      (node (ref "R20") (pin "2") (pinfunction "2_2") (pintype "passive"))
    )
    (net (code "57") (name "Net-(Tr2-Sec+)") (class "Default")
      (node (ref "C54") (pin "1") (pinfunction "1_1") (pintype "passive"))
      (node (ref "R152") (pin "1") (pinfunction "1_1") (pintype "passive"))
      (node (ref "R31") (pin "2") (pinfunction "2_2") (pintype "passive"))
      (node (ref "R32") (pin "2") (pinfunction "2_2") (pintype "passive"))
      (node (ref "Tr2") (pin "1") (pinfunction "Sec+_1") (pintype "passive"))
    )
    (net (code "58") (name "Vrefdac") (class "Default")
      (node (ref "C36") (pin "2") (pinfunction "2_2") (pintype "passive"))
      (node (ref "C37") (pin "1") (pinfunction "1_1") (pintype "passive"))
      (node (ref "IC28") (pin "1") (pinfunction "+V_1") (pintype "passive"))
      (node (ref "IC5") (pin "2") (pinfunction "VREF_2") (pintype "input"))
      (node (ref "IC8") (pin "2") (pinfunction "VREF_2") (pintype "input"))
      (node (ref "R145") (pin "1") (pinfunction "1_1") (pintype "passive"))
    )
    (net (code "59") (name "unconnected-(IC12C-Y-Pad8)") (class "Default")
      (node (ref "IC12") (pin "8") (pinfunction "Y_8") (pintype "tri_state"))
    )
    (net (code "60") (name "unconnected-(IC12D-Y-Pad11)") (class "Default")
      (node (ref "IC12") (pin "11") (pinfunction "Y_11") (pintype "tri_state"))
    )
    (net (code "61") (name "unconnected-(IC22-E-Pad1)") (class "Default")
      (node (ref "IC22") (pin "1") (pinfunction "E_1") (pintype "input+no_connect"))
    )
    (net (code "62") (name "unconnected-(IC28-NC-Pad3)") (class "Default")
      (node (ref "IC28") (pin "3") (pinfunction "NC_3") (pintype "passive"))
    )
  )
)
